# Hocki-Control.net
KiCad netlist of a schematic drawn in EAGLE
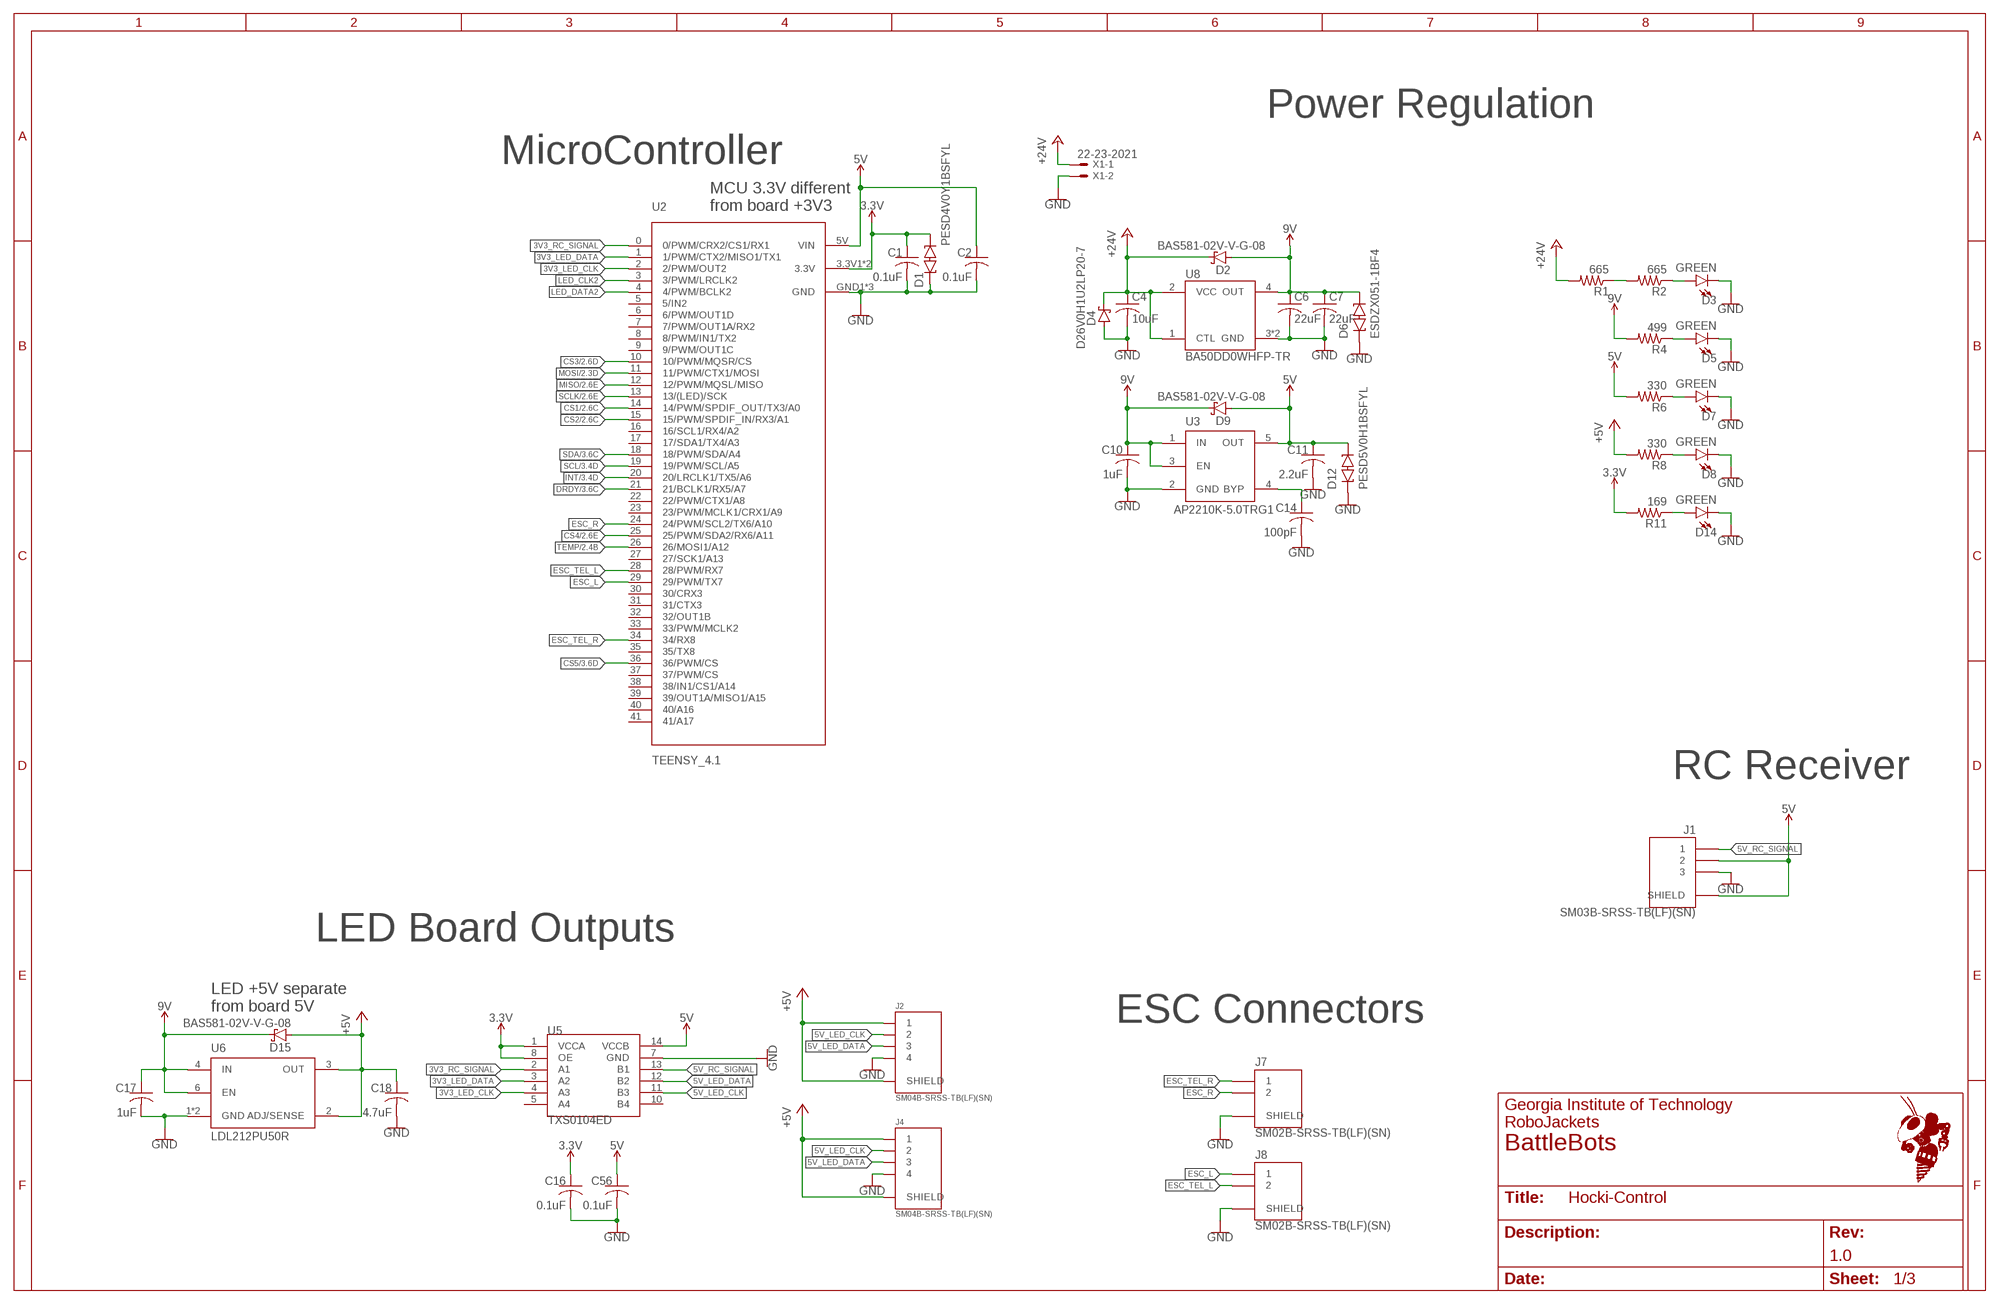
[diagram p0: schematic, sheet 1]
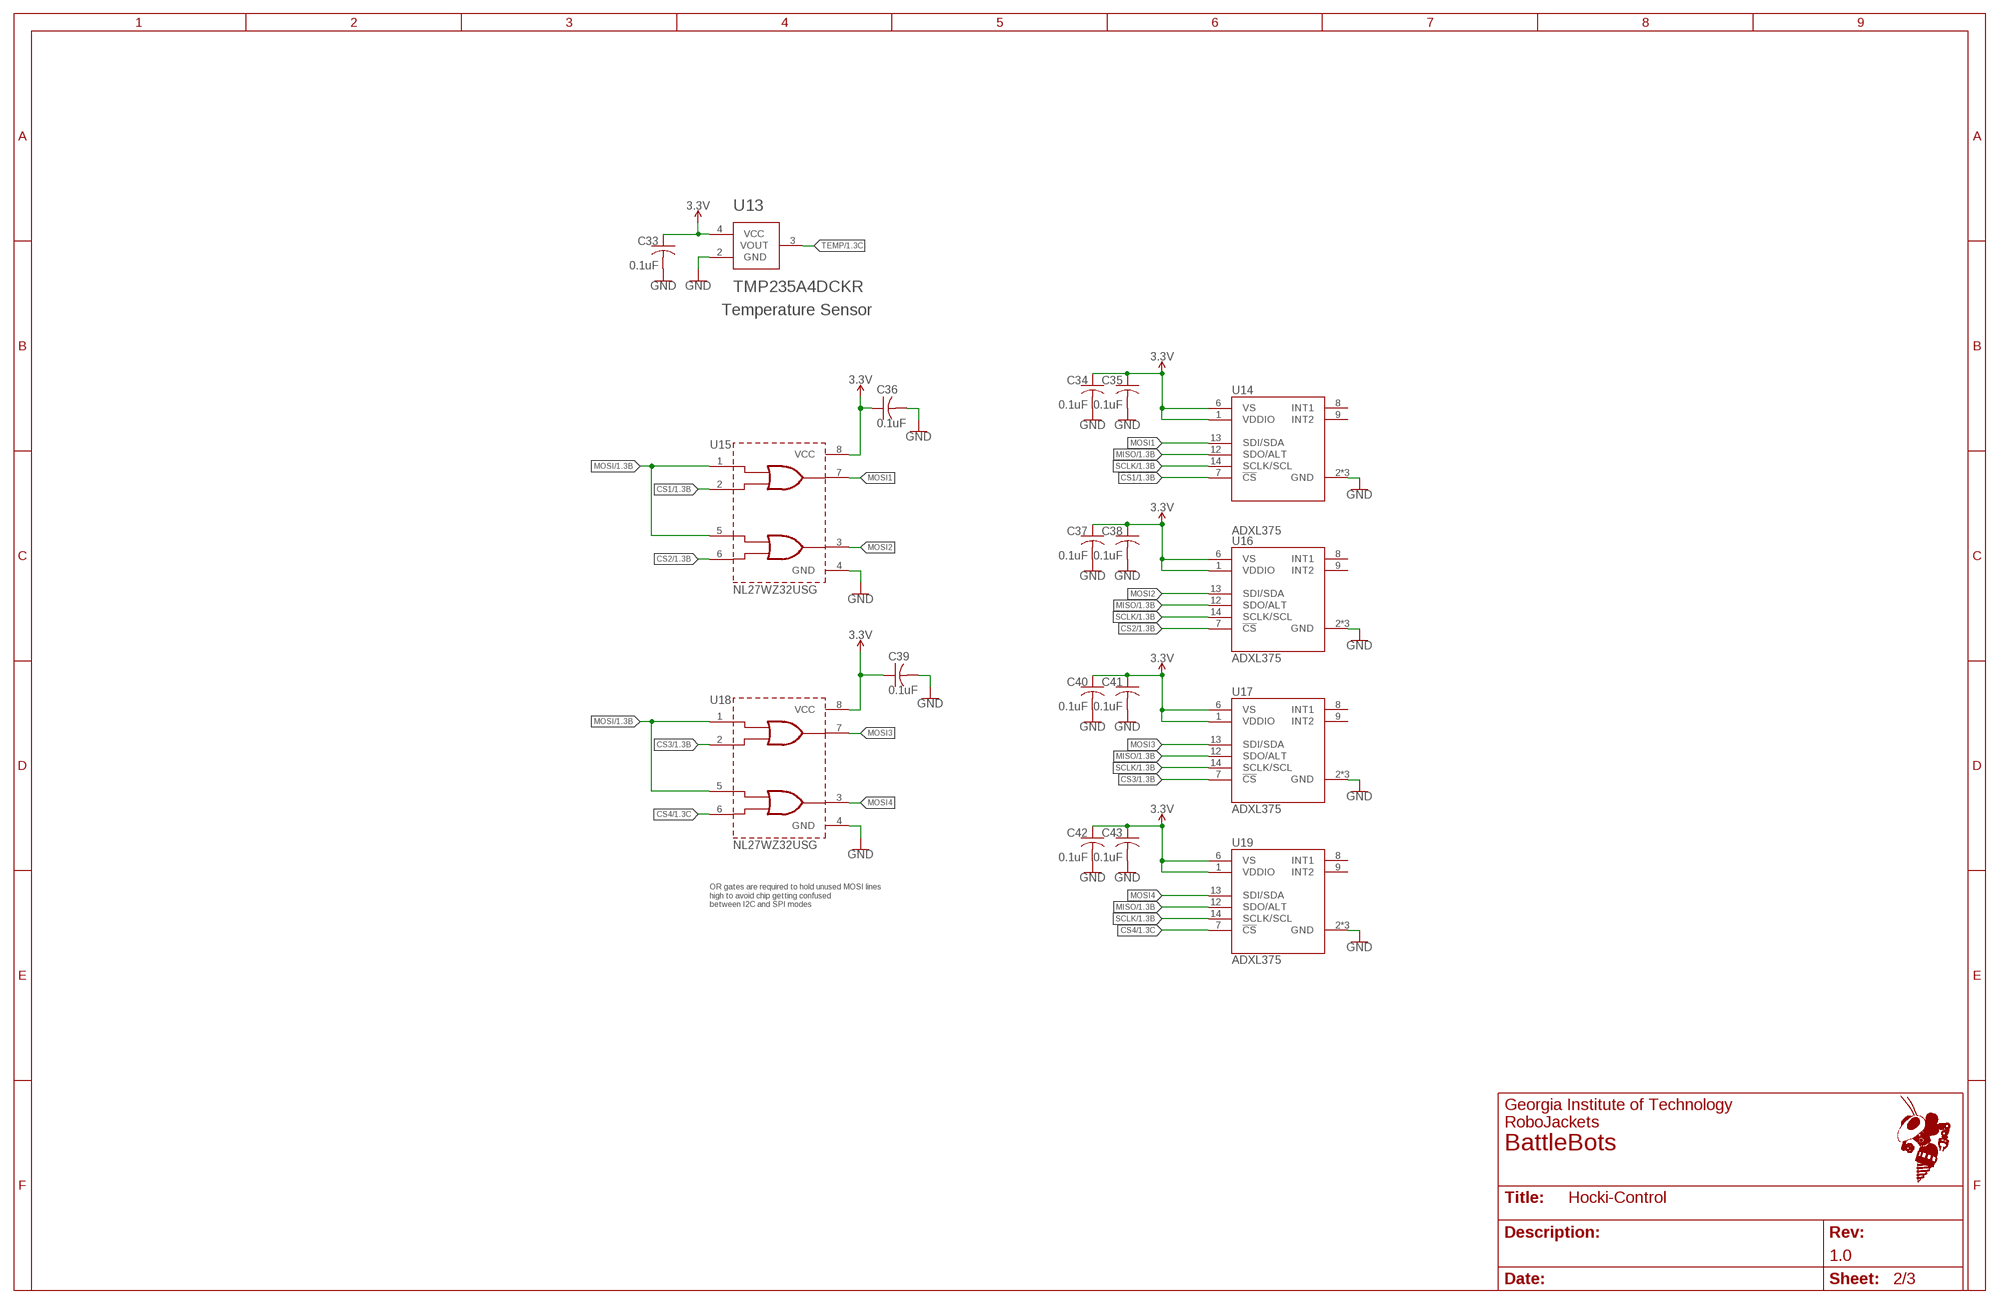
[diagram p1: schematic, sheet 2]
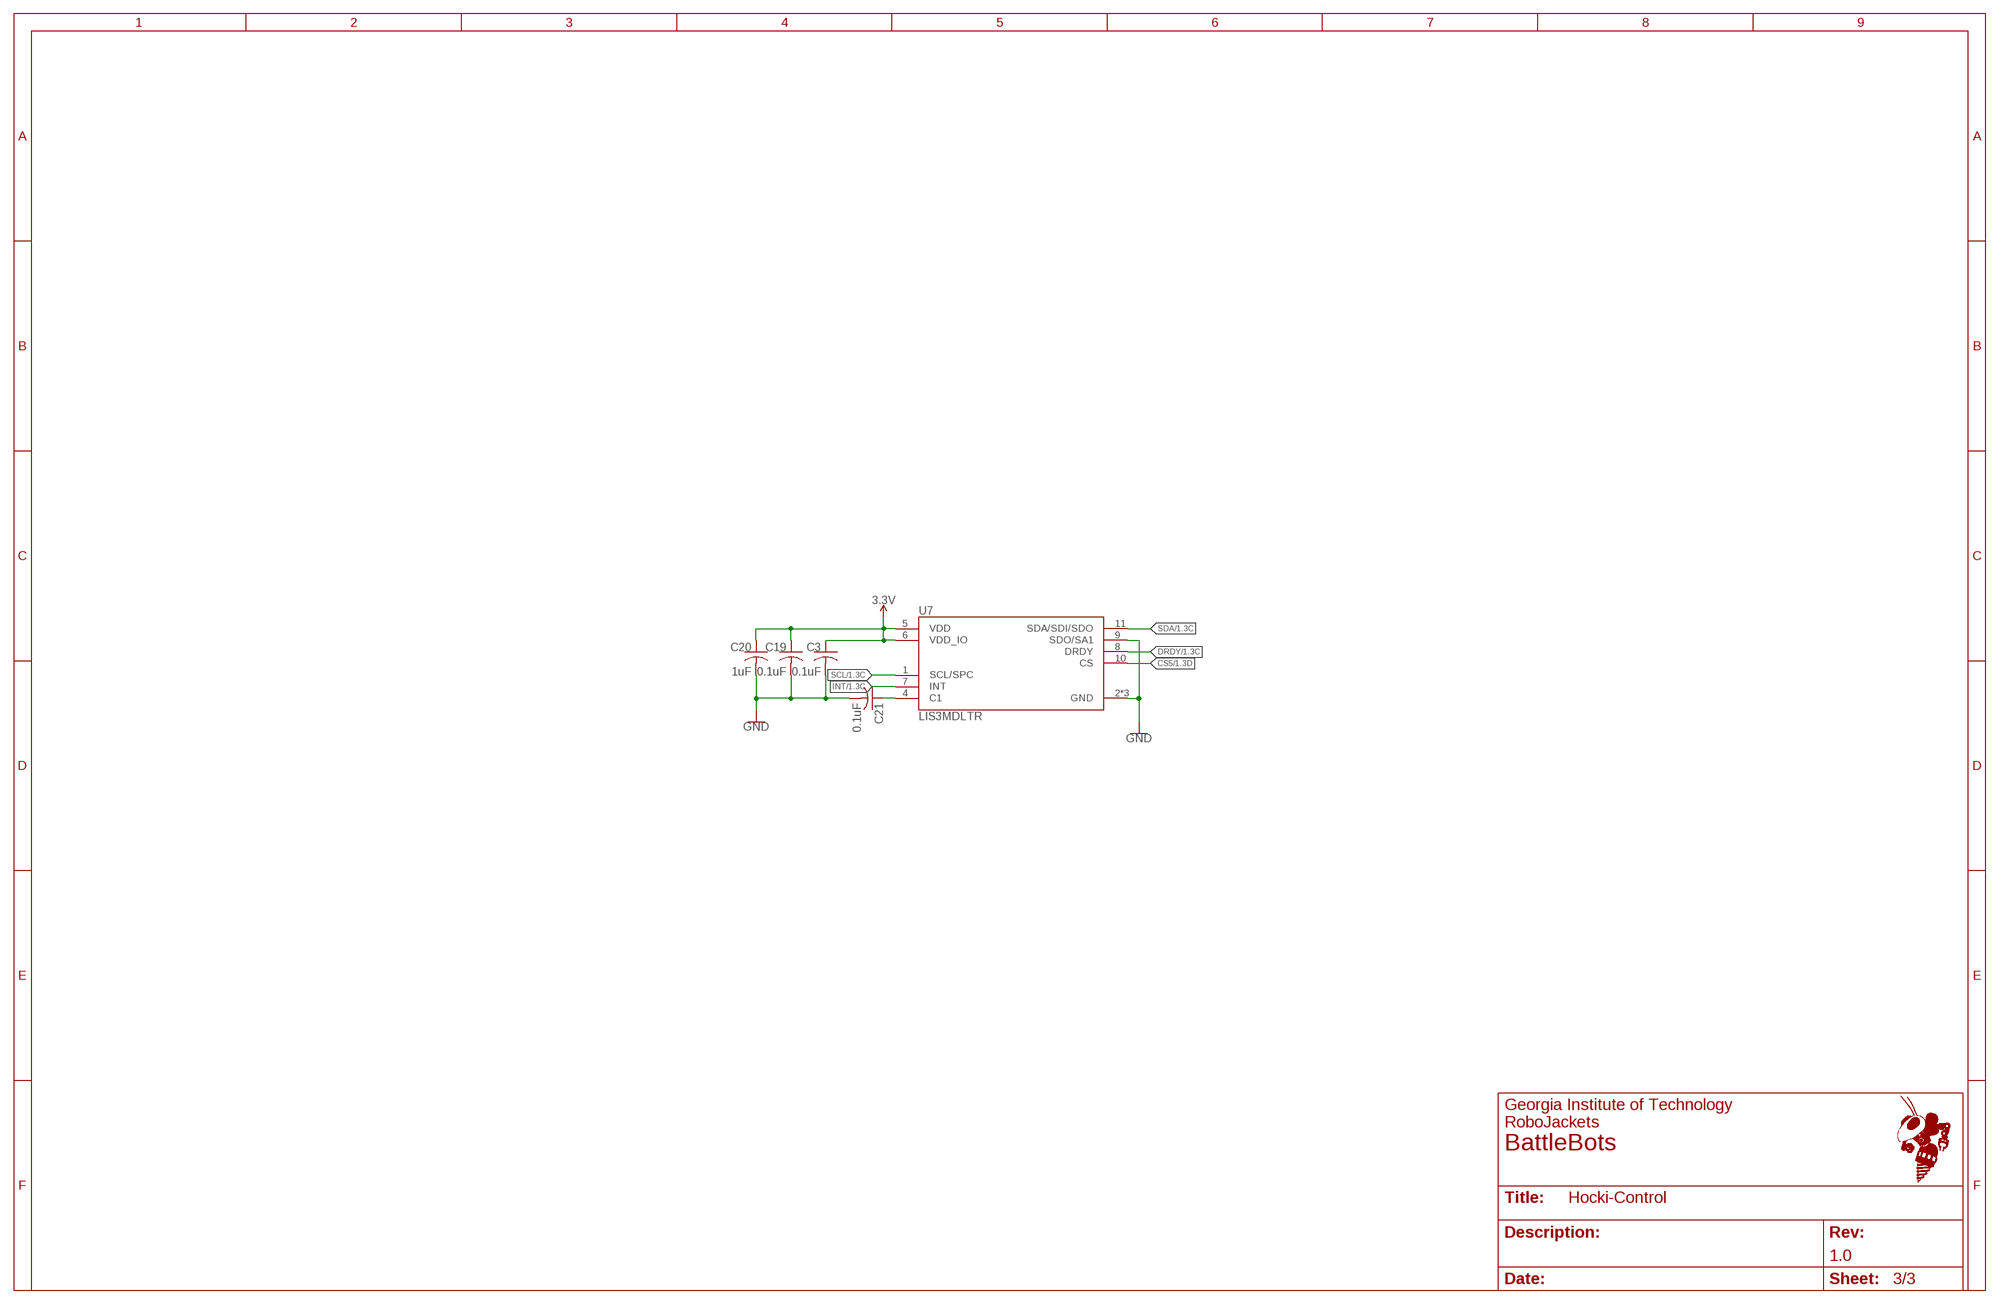
[diagram p2: schematic, sheet 3]

(export (version "E")
  (design (tool "Eeschema 10.0.6"))
  (components
    (comp (ref "C3")
      (value "0.1uF")
      (footprint "eagle-import:C0603")
      (libsource (lib "eagle-import") (part "C-USC0603"))
    )
    (comp (ref "C19")
      (value "0.1uF")
      (footprint "eagle-import:C0603")
      (libsource (lib "eagle-import") (part "C-USC0603"))
    )
    (comp (ref "C20")
      (value "1uF")
      (footprint "eagle-import:C0603")
      (libsource (lib "eagle-import") (part "C-USC0603"))
    )
    (comp (ref "C21")
      (value "0.1uF")
      (footprint "eagle-import:C0603")
      (libsource (lib "eagle-import") (part "C-USC0603"))
    )
    (comp (ref "U7")
      (value "LIS3MDLTR")
      (footprint "eagle-import:LGA-12_2X2X1_STM")
      (libsource (lib "eagle-import") (part "LIS3MDLTR"))
    )
    (comp (ref "C1")
      (value "0.1uF")
      (footprint "eagle-import:C0603")
      (libsource (lib "eagle-import") (part "C-USC0603"))
    )
    (comp (ref "C2")
      (value "0.1uF")
      (footprint "eagle-import:C0603")
      (libsource (lib "eagle-import") (part "C-USC0603"))
    )
    (comp (ref "C4")
      (value "10uF")
      (footprint "eagle-import:C1206")
      (libsource (lib "eagle-import") (part "C-USC1206"))
    )
    (comp (ref "C6")
      (value "22uF")
      (footprint "eagle-import:C1206")
      (libsource (lib "eagle-import") (part "C-USC1206"))
    )
    (comp (ref "C7")
      (value "22uF")
      (footprint "eagle-import:C1206")
      (libsource (lib "eagle-import") (part "C-USC1206"))
    )
    (comp (ref "C10")
      (value "1uF")
      (footprint "eagle-import:C0603")
      (libsource (lib "eagle-import") (part "C-USC0603"))
    )
    (comp (ref "C11")
      (value "2.2uF")
      (footprint "eagle-import:C0603")
      (libsource (lib "eagle-import") (part "C-USC0603"))
    )
    (comp (ref "C14")
      (value "100pF")
      (footprint "eagle-import:C0603")
      (libsource (lib "eagle-import") (part "C-USC0603"))
    )
    (comp (ref "C16")
      (value "0.1uF")
      (footprint "eagle-import:C0603")
      (libsource (lib "eagle-import") (part "C-USC0603"))
    )
    (comp (ref "C17")
      (value "1uF")
      (footprint "eagle-import:C0603")
      (libsource (lib "eagle-import") (part "C-USC0603"))
    )
    (comp (ref "C18")
      (value "4.7uF")
      (footprint "eagle-import:C0603")
      (libsource (lib "eagle-import") (part "C-USC0603"))
    )
    (comp (ref "C56")
      (value "0.1uF")
      (footprint "eagle-import:C0603")
      (libsource (lib "eagle-import") (part "C-USC0603"))
    )
    (comp (ref "D1")
      (value "PESD4V0Y1BSFYL")
      (footprint "eagle-import:DSN0603-2")
      (libsource (lib "eagle-import") (part "PESD4V0Y1BSFYL"))
    )
    (comp (ref "D2")
      (value "BAS581-02V-V-G-08")
      (footprint "eagle-import:SOD-523")
      (libsource (lib "eagle-import") (part "BAS581-02V-V-G-08"))
    )
    (comp (ref "D3")
      (value "GREEN")
      (footprint "eagle-import:LED-0603")
      (libsource (lib "eagle-import") (part "LED-GREEN0603"))
    )
    (comp (ref "D4")
      (value "D26V0H1U2LP20-7")
      (footprint "eagle-import:D26V0H1U2LP20-7")
      (libsource (lib "eagle-import") (part "D26V0H1U2LP20-7"))
    )
    (comp (ref "D5")
      (value "GREEN")
      (footprint "eagle-import:LED-0603")
      (libsource (lib "eagle-import") (part "LED-GREEN0603"))
    )
    (comp (ref "D6")
      (value "ESDZX051-1BF4")
      (footprint "eagle-import:DSN0603-2")
      (libsource (lib "eagle-import") (part "ESDZX051-1BF4"))
    )
    (comp (ref "D7")
      (value "GREEN")
      (footprint "eagle-import:LED-0603")
      (libsource (lib "eagle-import") (part "LED-GREEN0603"))
    )
    (comp (ref "D8")
      (value "GREEN")
      (footprint "eagle-import:LED-0603")
      (libsource (lib "eagle-import") (part "LED-GREEN0603"))
    )
    (comp (ref "D9")
      (value "BAS581-02V-V-G-08")
      (footprint "eagle-import:SOD-523")
      (libsource (lib "eagle-import") (part "BAS581-02V-V-G-08"))
    )
    (comp (ref "D12")
      (value "PESD5V0H1BSFYL")
      (footprint "eagle-import:DSN0603-2")
      (libsource (lib "eagle-import") (part "PESD5V0H1BSFYL"))
    )
    (comp (ref "D14")
      (value "GREEN")
      (footprint "eagle-import:LED-0603")
      (libsource (lib "eagle-import") (part "LED-GREEN0603"))
    )
    (comp (ref "D15")
      (value "BAS581-02V-V-G-08")
      (footprint "eagle-import:SOD-523")
      (libsource (lib "eagle-import") (part "BAS581-02V-V-G-08"))
    )
    (comp (ref "J1")
      (value "SM03B-SRSS-TB(LF)(SN)")
      (footprint "eagle-import:SM03B-SRSS-TB(LF)(SN)")
      (libsource (lib "eagle-import") (part "SM03B-SRSS-TB(LF)(SN)"))
    )
    (comp (ref "J2")
      (value "SM04B-SRSS-TB(LF)(SN)")
      (footprint "eagle-import:SM04B-SRSS-TB(LF)(SN)")
      (libsource (lib "eagle-import") (part "SM04B-SRSS-TB(LF)(SN)"))
    )
    (comp (ref "J4")
      (value "SM04B-SRSS-TB(LF)(SN)")
      (footprint "eagle-import:SM04B-SRSS-TB(LF)(SN)")
      (libsource (lib "eagle-import") (part "SM04B-SRSS-TB(LF)(SN)"))
    )
    (comp (ref "J7")
      (value "SM02B-SRSS-TB(LF)(SN)")
      (footprint "eagle-import:SM02B-SRSS-TB(LF)(SN)")
      (libsource (lib "eagle-import") (part "SM02B-SRSS-TB(LF)(SN)"))
    )
    (comp (ref "J8")
      (value "SM02B-SRSS-TB(LF)(SN)")
      (footprint "eagle-import:SM02B-SRSS-TB(LF)(SN)")
      (libsource (lib "eagle-import") (part "SM02B-SRSS-TB(LF)(SN)"))
    )
    (comp (ref "R1")
      (value "665")
      (footprint "eagle-import:R0603")
      (libsource (lib "eagle-import") (part "R-US_R0603"))
    )
    (comp (ref "R2")
      (value "665")
      (footprint "eagle-import:R0603")
      (libsource (lib "eagle-import") (part "R-US_R0603"))
    )
    (comp (ref "R4")
      (value "499")
      (footprint "eagle-import:R0603")
      (libsource (lib "eagle-import") (part "R-US_R0603"))
    )
    (comp (ref "R6")
      (value "330")
      (footprint "eagle-import:R0603")
      (libsource (lib "eagle-import") (part "R-US_R0603"))
    )
    (comp (ref "R8")
      (value "330")
      (footprint "eagle-import:R0603")
      (libsource (lib "eagle-import") (part "R-US_R0603"))
    )
    (comp (ref "R11")
      (value "169")
      (footprint "eagle-import:R0603")
      (libsource (lib "eagle-import") (part "R-US_R0603"))
    )
    (comp (ref "U2")
      (value "TEENSY_4.1")
      (footprint "eagle-import:TEENSY_4.1")
      (libsource (lib "eagle-import") (part "TEENSY_4.1"))
    )
    (comp (ref "U3")
      (value "AP2210K-5.0TRG1")
      (footprint "eagle-import:SOT-23-5")
      (libsource (lib "eagle-import") (part "AP2210K-TRG15.0"))
    )
    (comp (ref "U5")
      (value "TXS0104ED")
      (footprint "eagle-import:14-SOIC")
      (libsource (lib "eagle-import") (part "TXS0104ED"))
    )
    (comp (ref "U6")
      (value "LDL212PU50R")
      (footprint "eagle-import:DFN6(3X3)")
      (libsource (lib "eagle-import") (part "LDL212PU50R"))
    )
    (comp (ref "U8")
      (value "BA50DD0WHFP-TR")
      (footprint "eagle-import:HRP5")
      (libsource (lib "eagle-import") (part "BA50DD0WHFP-TR"))
    )
    (comp (ref "X1")
      (value "22-23-2021")
      (footprint "eagle-import:22-23-2021")
      (fields (field (name "MF") "MOLEX"))
      (libsource (lib "eagle-import") (part "22-23-2021"))
    )
    (comp (ref "C33")
      (value "0.1uF")
      (footprint "eagle-import:C0603")
      (libsource (lib "eagle-import") (part "C-USC0603"))
    )
    (comp (ref "C34")
      (value "0.1uF")
      (footprint "eagle-import:C0603")
      (libsource (lib "eagle-import") (part "C-USC0603"))
    )
    (comp (ref "C35")
      (value "0.1uF")
      (footprint "eagle-import:C0603")
      (libsource (lib "eagle-import") (part "C-USC0603"))
    )
    (comp (ref "C36")
      (value "0.1uF")
      (footprint "eagle-import:C0603")
      (libsource (lib "eagle-import") (part "C-USC0603"))
    )
    (comp (ref "C37")
      (value "0.1uF")
      (footprint "eagle-import:C0603")
      (libsource (lib "eagle-import") (part "C-USC0603"))
    )
    (comp (ref "C38")
      (value "0.1uF")
      (footprint "eagle-import:C0603")
      (libsource (lib "eagle-import") (part "C-USC0603"))
    )
    (comp (ref "C39")
      (value "0.1uF")
      (footprint "eagle-import:C0603")
      (libsource (lib "eagle-import") (part "C-USC0603"))
    )
    (comp (ref "C40")
      (value "0.1uF")
      (footprint "eagle-import:C0603")
      (libsource (lib "eagle-import") (part "C-USC0603"))
    )
    (comp (ref "C41")
      (value "0.1uF")
      (footprint "eagle-import:C0603")
      (libsource (lib "eagle-import") (part "C-USC0603"))
    )
    (comp (ref "C42")
      (value "0.1uF")
      (footprint "eagle-import:C0603")
      (libsource (lib "eagle-import") (part "C-USC0603"))
    )
    (comp (ref "C43")
      (value "0.1uF")
      (footprint "eagle-import:C0603")
      (libsource (lib "eagle-import") (part "C-USC0603"))
    )
    (comp (ref "U13")
      (value "TMP235A4DCKR")
      (footprint "eagle-import:SOT-353")
      (libsource (lib "eagle-import") (part "TMP235A4DCKR"))
    )
    (comp (ref "U14")
      (value "ADXL375")
      (footprint "eagle-import:14-LGA")
      (libsource (lib "eagle-import") (part "ADXL375"))
    )
    (comp (ref "U15")
      (value "NL27WZ32USG")
      (footprint "eagle-import:US8")
      (libsource (lib "eagle-import") (part "NL27WZ32USG"))
    )
    (comp (ref "U16")
      (value "ADXL375")
      (footprint "eagle-import:14-LGA")
      (libsource (lib "eagle-import") (part "ADXL375"))
    )
    (comp (ref "U17")
      (value "ADXL375")
      (footprint "eagle-import:14-LGA")
      (libsource (lib "eagle-import") (part "ADXL375"))
    )
    (comp (ref "U18")
      (value "NL27WZ32USG")
      (footprint "eagle-import:US8")
      (libsource (lib "eagle-import") (part "NL27WZ32USG"))
    )
    (comp (ref "U19")
      (value "ADXL375")
      (footprint "eagle-import:14-LGA")
      (libsource (lib "eagle-import") (part "ADXL375"))
    )
  )
  (nets
    (net (code "1") (name "+5V") (class "Default")
      (node (ref "C18") (pin "1") (pinfunction "1_1") (pintype "passive"))
      (node (ref "D15") (pin "2") (pinfunction "A_2") (pintype "passive"))
      (node (ref "J2") (pin "1") (pinfunction "1_1") (pintype "passive"))
      (node (ref "J2") (pin "S1") (pinfunction "SHIELD_S1") (pintype "passive"))
      (node (ref "J2") (pin "S2") (pinfunction "SHIELD_S2") (pintype "passive"))
      (node (ref "J4") (pin "1") (pinfunction "1_1") (pintype "passive"))
      (node (ref "J4") (pin "S1") (pinfunction "SHIELD_S1") (pintype "passive"))
      (node (ref "J4") (pin "S2") (pinfunction "SHIELD_S2") (pintype "passive"))
      (node (ref "R8") (pin "2") (pinfunction "2_2") (pintype "passive"))
      (node (ref "U6") (pin "2") (pinfunction "ADJ/SENSE_2") (pintype "bidirectional"))
      (node (ref "U6") (pin "3") (pinfunction "OUT_3") (pintype "passive"))
    )
    (net (code "2") (name "+24V") (class "Default")
      (node (ref "C4") (pin "1") (pinfunction "1_1") (pintype "passive"))
      (node (ref "D2") (pin "1") (pinfunction "C_1") (pintype "passive"))
      (node (ref "D4") (pin "1") (pinfunction "C_1") (pintype "passive"))
      (node (ref "R1") (pin "2") (pinfunction "2_2") (pintype "passive"))
      (node (ref "U8") (pin "1") (pinfunction "CTL_1") (pintype "input"))
      (node (ref "U8") (pin "2") (pinfunction "VCC_2") (pintype "power_in"))
      (node (ref "X1") (pin "1") (pinfunction "S_1") (pintype "passive"))
    )
    (net (code "3") (name "3.3V") (class "Default")
      (node (ref "C1") (pin "1") (pinfunction "1_1") (pintype "passive"))
      (node (ref "C16") (pin "1") (pinfunction "1_1") (pintype "passive"))
      (node (ref "C19") (pin "1") (pinfunction "1_1") (pintype "passive"))
      (node (ref "C20") (pin "1") (pinfunction "1_1") (pintype "passive"))
      (node (ref "C3") (pin "1") (pinfunction "1_1") (pintype "passive"))
      (node (ref "C33") (pin "1") (pinfunction "1_1") (pintype "passive"))
      (node (ref "C34") (pin "1") (pinfunction "1_1") (pintype "passive"))
      (node (ref "C35") (pin "1") (pinfunction "1_1") (pintype "passive"))
      (node (ref "C36") (pin "1") (pinfunction "1_1") (pintype "passive"))
      (node (ref "C37") (pin "1") (pinfunction "1_1") (pintype "passive"))
      (node (ref "C38") (pin "1") (pinfunction "1_1") (pintype "passive"))
      (node (ref "C39") (pin "1") (pinfunction "1_1") (pintype "passive"))
      (node (ref "C40") (pin "1") (pinfunction "1_1") (pintype "passive"))
      (node (ref "C41") (pin "1") (pinfunction "1_1") (pintype "passive"))
      (node (ref "C42") (pin "1") (pinfunction "1_1") (pintype "passive"))
      (node (ref "C43") (pin "1") (pinfunction "1_1") (pintype "passive"))
      (node (ref "D1") (pin "C2") (pinfunction "C2_C2") (pintype "passive"))
      (node (ref "R11") (pin "2") (pinfunction "2_2") (pintype "passive"))
      (node (ref "U13") (pin "4") (pinfunction "VCC_4") (pintype "passive"))
      (node (ref "U14") (pin "1") (pinfunction "VDDIO_1") (pintype "passive"))
      (node (ref "U14") (pin "6") (pinfunction "VS_6") (pintype "passive"))
      (node (ref "U15") (pin "8") (pinfunction "VCC_8") (pintype "passive"))
      (node (ref "U16") (pin "1") (pinfunction "VDDIO_1") (pintype "passive"))
      (node (ref "U16") (pin "6") (pinfunction "VS_6") (pintype "passive"))
      (node (ref "U17") (pin "1") (pinfunction "VDDIO_1") (pintype "passive"))
      (node (ref "U17") (pin "6") (pinfunction "VS_6") (pintype "passive"))
      (node (ref "U18") (pin "8") (pinfunction "VCC_8") (pintype "passive"))
      (node (ref "U19") (pin "1") (pinfunction "VDDIO_1") (pintype "passive"))
      (node (ref "U19") (pin "6") (pinfunction "VS_6") (pintype "passive"))
      (node (ref "U2") (pin "3.3V1") (pinfunction "3.3V_3.3V1") (pintype "passive"))
      (node (ref "U2") (pin "3.3V2") (pinfunction "3.3V_3.3V2") (pintype "passive"))
      (node (ref "U5") (pin "1") (pinfunction "VCCA_1") (pintype "passive"))
      (node (ref "U5") (pin "8") (pinfunction "OE_8") (pintype "passive"))
      (node (ref "U7") (pin "5") (pinfunction "VDD_5") (pintype "passive"))
      (node (ref "U7") (pin "6") (pinfunction "VDD_IO_6") (pintype "passive"))
    )
    (net (code "4") (name "3V3_LED_CLK") (class "Default")
      (node (ref "U2") (pin "2") (pinfunction "2/PWM/OUT2_2") (pintype "passive"))
      (node (ref "U5") (pin "4") (pinfunction "A3_4") (pintype "passive"))
    )
    (net (code "5") (name "3V3_LED_DATA") (class "Default")
      (node (ref "U2") (pin "1") (pinfunction "1/PWM/CTX2/MISO1/TX1_1") (pintype "passive"))
      (node (ref "U5") (pin "3") (pinfunction "A2_3") (pintype "passive"))
    )
    (net (code "6") (name "3V3_RC_SIGNAL") (class "Default")
      (node (ref "U2") (pin "0") (pinfunction "0/PWM/CRX2/CS1/RX1_0") (pintype "passive"))
      (node (ref "U5") (pin "2") (pinfunction "A1_2") (pintype "passive"))
    )
    (net (code "7") (name "5V") (class "Default")
      (node (ref "C11") (pin "1") (pinfunction "1_1") (pintype "passive"))
      (node (ref "C2") (pin "1") (pinfunction "1_1") (pintype "passive"))
      (node (ref "C56") (pin "1") (pinfunction "1_1") (pintype "passive"))
      (node (ref "D12") (pin "C2") (pinfunction "C2_C2") (pintype "passive"))
      (node (ref "D9") (pin "2") (pinfunction "A_2") (pintype "passive"))
      (node (ref "J1") (pin "2") (pinfunction "2_2") (pintype "passive"))
      (node (ref "J1") (pin "S1") (pinfunction "SHIELD_S1") (pintype "passive"))
      (node (ref "J1") (pin "S2") (pinfunction "SHIELD_S2") (pintype "passive"))
      (node (ref "R6") (pin "2") (pinfunction "2_2") (pintype "passive"))
      (node (ref "U2") (pin "5V") (pinfunction "VIN_5V") (pintype "passive"))
      (node (ref "U3") (pin "5") (pinfunction "OUT_5") (pintype "passive"))
      (node (ref "U5") (pin "14") (pinfunction "VCCB_14") (pintype "passive"))
    )
    (net (code "8") (name "5V_LED_CLK") (class "Default")
      (node (ref "J2") (pin "2") (pinfunction "2_2") (pintype "passive"))
      (node (ref "J4") (pin "2") (pinfunction "2_2") (pintype "passive"))
      (node (ref "U5") (pin "11") (pinfunction "B3_11") (pintype "passive"))
    )
    (net (code "9") (name "5V_LED_DATA") (class "Default")
      (node (ref "J2") (pin "3") (pinfunction "3_3") (pintype "passive"))
      (node (ref "J4") (pin "3") (pinfunction "3_3") (pintype "passive"))
      (node (ref "U5") (pin "12") (pinfunction "B2_12") (pintype "passive"))
    )
    (net (code "10") (name "5V_RC_SIGNAL") (class "Default")
      (node (ref "J1") (pin "1") (pinfunction "1_1") (pintype "passive"))
      (node (ref "U5") (pin "13") (pinfunction "B1_13") (pintype "passive"))
    )
    (net (code "11") (name "9V") (class "Default")
      (node (ref "C10") (pin "1") (pinfunction "1_1") (pintype "passive"))
      (node (ref "C17") (pin "1") (pinfunction "1_1") (pintype "passive"))
      (node (ref "C6") (pin "1") (pinfunction "1_1") (pintype "passive"))
      (node (ref "C7") (pin "1") (pinfunction "1_1") (pintype "passive"))
      (node (ref "D15") (pin "1") (pinfunction "C_1") (pintype "passive"))
      (node (ref "D2") (pin "2") (pinfunction "A_2") (pintype "passive"))
      (node (ref "D6") (pin "C2") (pinfunction "C2_C2") (pintype "passive"))
      (node (ref "D9") (pin "1") (pinfunction "C_1") (pintype "passive"))
      (node (ref "R4") (pin "2") (pinfunction "2_2") (pintype "passive"))
      (node (ref "U3") (pin "1") (pinfunction "IN_1") (pintype "passive"))
      (node (ref "U3") (pin "3") (pinfunction "EN_3") (pintype "passive"))
      (node (ref "U6") (pin "4") (pinfunction "IN_4") (pintype "passive"))
      (node (ref "U6") (pin "6") (pinfunction "EN_6") (pintype "passive"))
      (node (ref "U8") (pin "4") (pinfunction "OUT_4") (pintype "output"))
    )
    (net (code "12") (name "CS1") (class "Default")
      (node (ref "U14") (pin "7") (pinfunction "~{CS}_7") (pintype "passive"))
      (node (ref "U15") (pin "2") (pinfunction "B1_2") (pintype "passive"))
      (node (ref "U2") (pin "14") (pinfunction "14/PWM/SPDIF_OUT/TX3/A0_14") (pintype "passive"))
    )
    (net (code "13") (name "CS2") (class "Default")
      (node (ref "U15") (pin "6") (pinfunction "B2_6") (pintype "passive"))
      (node (ref "U16") (pin "7") (pinfunction "~{CS}_7") (pintype "passive"))
      (node (ref "U2") (pin "15") (pinfunction "15/PWM/SPDIF_IN/RX3/A1_15") (pintype "passive"))
    )
    (net (code "14") (name "CS3") (class "Default")
      (node (ref "U17") (pin "7") (pinfunction "~{CS}_7") (pintype "passive"))
      (node (ref "U18") (pin "2") (pinfunction "B1_2") (pintype "passive"))
      (node (ref "U2") (pin "10") (pinfunction "10/PWM/MQSR/CS_10") (pintype "passive"))
    )
    (net (code "15") (name "CS4") (class "Default")
      (node (ref "U18") (pin "6") (pinfunction "B2_6") (pintype "passive"))
      (node (ref "U19") (pin "7") (pinfunction "~{CS}_7") (pintype "passive"))
      (node (ref "U2") (pin "25") (pinfunction "25/PWM/SDA2/RX6/A11_25") (pintype "passive"))
    )
    (net (code "16") (name "CS5") (class "Default")
      (node (ref "U2") (pin "36") (pinfunction "36/PWM/CS_36") (pintype "passive"))
      (node (ref "U7") (pin "10") (pinfunction "CS_10") (pintype "passive"))
    )
    (net (code "17") (name "DRDY") (class "Default")
      (node (ref "U2") (pin "21") (pinfunction "21/BCLK1/RX5/A7_21") (pintype "passive"))
      (node (ref "U7") (pin "8") (pinfunction "DRDY_8") (pintype "passive"))
    )
    (net (code "18") (name "ESC_L") (class "Default")
      (node (ref "J8") (pin "1") (pinfunction "1_1") (pintype "passive"))
      (node (ref "U2") (pin "29") (pinfunction "29/PWM/TX7_29") (pintype "passive"))
    )
    (net (code "19") (name "ESC_R") (class "Default")
      (node (ref "J7") (pin "2") (pinfunction "2_2") (pintype "passive"))
      (node (ref "U2") (pin "24") (pinfunction "24/PWM/SCL2/TX6/A10_24") (pintype "passive"))
    )
    (net (code "20") (name "ESC_TEL_L") (class "Default")
      (node (ref "J8") (pin "2") (pinfunction "2_2") (pintype "passive"))
      (node (ref "U2") (pin "28") (pinfunction "28/PWM/RX7_28") (pintype "passive"))
    )
    (net (code "21") (name "ESC_TEL_R") (class "Default")
      (node (ref "J7") (pin "1") (pinfunction "1_1") (pintype "passive"))
      (node (ref "U2") (pin "34") (pinfunction "34/RX8_34") (pintype "passive"))
    )
    (net (code "22") (name "GND") (class "Default")
      (node (ref "C1") (pin "2") (pinfunction "2_2") (pintype "passive"))
      (node (ref "C10") (pin "2") (pinfunction "2_2") (pintype "passive"))
      (node (ref "C11") (pin "2") (pinfunction "2_2") (pintype "passive"))
      (node (ref "C14") (pin "2") (pinfunction "2_2") (pintype "passive"))
      (node (ref "C16") (pin "2") (pinfunction "2_2") (pintype "passive"))
      (node (ref "C17") (pin "2") (pinfunction "2_2") (pintype "passive"))
      (node (ref "C18") (pin "2") (pinfunction "2_2") (pintype "passive"))
      (node (ref "C19") (pin "2") (pinfunction "2_2") (pintype "passive"))
      (node (ref "C2") (pin "2") (pinfunction "2_2") (pintype "passive"))
      (node (ref "C20") (pin "2") (pinfunction "2_2") (pintype "passive"))
      (node (ref "C21") (pin "2") (pinfunction "2_2") (pintype "passive"))
      (node (ref "C3") (pin "2") (pinfunction "2_2") (pintype "passive"))
      (node (ref "C33") (pin "2") (pinfunction "2_2") (pintype "passive"))
      (node (ref "C34") (pin "2") (pinfunction "2_2") (pintype "passive"))
      (node (ref "C35") (pin "2") (pinfunction "2_2") (pintype "passive"))
      (node (ref "C36") (pin "2") (pinfunction "2_2") (pintype "passive"))
      (node (ref "C37") (pin "2") (pinfunction "2_2") (pintype "passive"))
      (node (ref "C38") (pin "2") (pinfunction "2_2") (pintype "passive"))
      (node (ref "C39") (pin "2") (pinfunction "2_2") (pintype "passive"))
      (node (ref "C4") (pin "2") (pinfunction "2_2") (pintype "passive"))
      (node (ref "C40") (pin "2") (pinfunction "2_2") (pintype "passive"))
      (node (ref "C41") (pin "2") (pinfunction "2_2") (pintype "passive"))
      (node (ref "C42") (pin "2") (pinfunction "2_2") (pintype "passive"))
      (node (ref "C43") (pin "2") (pinfunction "2_2") (pintype "passive"))
      (node (ref "C56") (pin "2") (pinfunction "2_2") (pintype "passive"))
      (node (ref "C6") (pin "2") (pinfunction "2_2") (pintype "passive"))
      (node (ref "C7") (pin "2") (pinfunction "2_2") (pintype "passive"))
      (node (ref "D1") (pin "C1") (pinfunction "C1_C1") (pintype "passive"))
      (node (ref "D12") (pin "C1") (pinfunction "C1_C1") (pintype "passive"))
      (node (ref "D14") (pin "C") (pinfunction "C_C") (pintype "passive"))
      (node (ref "D3") (pin "C") (pinfunction "C_C") (pintype "passive"))
      (node (ref "D4") (pin "2") (pinfunction "A_2") (pintype "passive"))
      (node (ref "D5") (pin "C") (pinfunction "C_C") (pintype "passive"))
      (node (ref "D6") (pin "C1") (pinfunction "C1_C1") (pintype "passive"))
      (node (ref "D7") (pin "C") (pinfunction "C_C") (pintype "passive"))
      (node (ref "D8") (pin "C") (pinfunction "C_C") (pintype "passive"))
      (node (ref "J1") (pin "3") (pinfunction "3_3") (pintype "passive"))
      (node (ref "J2") (pin "4") (pinfunction "4_4") (pintype "passive"))
      (node (ref "J4") (pin "4") (pinfunction "4_4") (pintype "passive"))
      (node (ref "J7") (pin "S1") (pinfunction "SHIELD_S1") (pintype "passive"))
      (node (ref "J7") (pin "S2") (pinfunction "SHIELD_S2") (pintype "passive"))
      (node (ref "J8") (pin "S1") (pinfunction "SHIELD_S1") (pintype "passive"))
      (node (ref "J8") (pin "S2") (pinfunction "SHIELD_S2") (pintype "passive"))
      (node (ref "U13") (pin "2") (pinfunction "GND_2") (pintype "passive"))
      (node (ref "U14") (pin "2") (pinfunction "GND_2") (pintype "passive"))
      (node (ref "U14") (pin "4") (pinfunction "GND_4") (pintype "passive"))
      (node (ref "U14") (pin "5") (pinfunction "GND_5") (pintype "passive"))
      (node (ref "U15") (pin "4") (pinfunction "GND_4") (pintype "passive"))
      (node (ref "U16") (pin "2") (pinfunction "GND_2") (pintype "passive"))
      (node (ref "U16") (pin "4") (pinfunction "GND_4") (pintype "passive"))
      (node (ref "U16") (pin "5") (pinfunction "GND_5") (pintype "passive"))
      (node (ref "U17") (pin "2") (pinfunction "GND_2") (pintype "passive"))
      (node (ref "U17") (pin "4") (pinfunction "GND_4") (pintype "passive"))
      (node (ref "U17") (pin "5") (pinfunction "GND_5") (pintype "passive"))
      (node (ref "U18") (pin "4") (pinfunction "GND_4") (pintype "passive"))
      (node (ref "U19") (pin "2") (pinfunction "GND_2") (pintype "passive"))
      (node (ref "U19") (pin "4") (pinfunction "GND_4") (pintype "passive"))
      (node (ref "U19") (pin "5") (pinfunction "GND_5") (pintype "passive"))
      (node (ref "U2") (pin "GND1") (pinfunction "GND_GND1") (pintype "passive"))
      (node (ref "U2") (pin "GND2") (pinfunction "GND_GND2") (pintype "passive"))
      (node (ref "U2") (pin "GND3") (pinfunction "GND_GND3") (pintype "passive"))
      (node (ref "U3") (pin "2") (pinfunction "GND_2") (pintype "passive"))
      (node (ref "U5") (pin "7") (pinfunction "GND_7") (pintype "passive"))
      (node (ref "U6") (pin "1") (pinfunction "GND_1") (pintype "passive"))
      (node (ref "U6") (pin "7") (pinfunction "GND_7") (pintype "passive"))
      (node (ref "U7") (pin "12") (pinfunction "GND_12") (pintype "passive"))
      (node (ref "U7") (pin "2") (pinfunction "GND_2") (pintype "passive"))
      (node (ref "U7") (pin "3") (pinfunction "GND_3") (pintype "passive"))
      (node (ref "U7") (pin "9") (pinfunction "SDO/SA1_9") (pintype "passive"))
      (node (ref "U8") (pin "3") (pinfunction "GND_3") (pintype "power_in"))
      (node (ref "U8") (pin "6") (pinfunction "GND_6") (pintype "power_in"))
      (node (ref "X1") (pin "2") (pinfunction "S_2") (pintype "passive"))
    )
    (net (code "23") (name "INT") (class "Default")
      (node (ref "U2") (pin "20") (pinfunction "20/LRCLK1/TX5/A6_20") (pintype "passive"))
      (node (ref "U7") (pin "7") (pinfunction "INT_7") (pintype "passive"))
    )
    (net (code "24") (name "LED_CLK2") (class "Default")
      (node (ref "U2") (pin "3") (pinfunction "3/PWM/LRCLK2_3") (pintype "passive"))
    )
    (net (code "25") (name "LED_DATA2") (class "Default")
      (node (ref "U2") (pin "4") (pinfunction "4/PWM/BCLK2_4") (pintype "passive"))
    )
    (net (code "26") (name "MISO") (class "Default")
      (node (ref "U14") (pin "12") (pinfunction "SDO/ALT_12") (pintype "passive"))
      (node (ref "U16") (pin "12") (pinfunction "SDO/ALT_12") (pintype "passive"))
      (node (ref "U17") (pin "12") (pinfunction "SDO/ALT_12") (pintype "passive"))
      (node (ref "U19") (pin "12") (pinfunction "SDO/ALT_12") (pintype "passive"))
      (node (ref "U2") (pin "12") (pinfunction "12/PWM/MQSL/MISO_12") (pintype "passive"))
    )
    (net (code "27") (name "MOSI") (class "Default")
      (node (ref "U15") (pin "1") (pinfunction "A1_1") (pintype "passive"))
      (node (ref "U15") (pin "5") (pinfunction "A2_5") (pintype "passive"))
      (node (ref "U18") (pin "1") (pinfunction "A1_1") (pintype "passive"))
      (node (ref "U18") (pin "5") (pinfunction "A2_5") (pintype "passive"))
      (node (ref "U2") (pin "11") (pinfunction "11/PWM/CTX1/MOSI_11") (pintype "passive"))
    )
    (net (code "28") (name "MOSI1") (class "Default")
      (node (ref "U14") (pin "13") (pinfunction "SDI/SDA_13") (pintype "passive"))
      (node (ref "U15") (pin "7") (pinfunction "Y1_7") (pintype "passive"))
    )
    (net (code "29") (name "MOSI2") (class "Default")
      (node (ref "U15") (pin "3") (pinfunction "Y2_3") (pintype "passive"))
      (node (ref "U16") (pin "13") (pinfunction "SDI/SDA_13") (pintype "passive"))
    )
    (net (code "30") (name "MOSI3") (class "Default")
      (node (ref "U17") (pin "13") (pinfunction "SDI/SDA_13") (pintype "passive"))
      (node (ref "U18") (pin "7") (pinfunction "Y1_7") (pintype "passive"))
    )
    (net (code "31") (name "MOSI4") (class "Default")
      (node (ref "U18") (pin "3") (pinfunction "Y2_3") (pintype "passive"))
      (node (ref "U19") (pin "13") (pinfunction "SDI/SDA_13") (pintype "passive"))
    )
    (net (code "32") (name "Net-(D3-PadA)") (class "Default")
      (node (ref "D3") (pin "A") (pinfunction "A_A") (pintype "passive"))
      (node (ref "R2") (pin "1") (pinfunction "1_1") (pintype "passive"))
    )
    (net (code "33") (name "Net-(D5-PadA)") (class "Default")
      (node (ref "D5") (pin "A") (pinfunction "A_A") (pintype "passive"))
      (node (ref "R4") (pin "1") (pinfunction "1_1") (pintype "passive"))
    )
    (net (code "34") (name "Net-(D7-PadA)") (class "Default")
      (node (ref "D7") (pin "A") (pinfunction "A_A") (pintype "passive"))
      (node (ref "R6") (pin "1") (pinfunction "1_1") (pintype "passive"))
    )
    (net (code "35") (name "Net-(D8-PadA)") (class "Default")
      (node (ref "D8") (pin "A") (pinfunction "A_A") (pintype "passive"))
      (node (ref "R8") (pin "1") (pinfunction "1_1") (pintype "passive"))
    )
    (net (code "36") (name "Net-(D14-PadA)") (class "Default")
      (node (ref "D14") (pin "A") (pinfunction "A_A") (pintype "passive"))
      (node (ref "R11") (pin "1") (pinfunction "1_1") (pintype "passive"))
    )
    (net (code "37") (name "Net-(R1-Pad1)") (class "Default")
      (node (ref "R1") (pin "1") (pinfunction "1_1") (pintype "passive"))
      (node (ref "R2") (pin "2") (pinfunction "2_2") (pintype "passive"))
    )
    (net (code "38") (name "Net-(U3-BYP)") (class "Default")
      (node (ref "C14") (pin "1") (pinfunction "1_1") (pintype "passive"))
      (node (ref "U3") (pin "4") (pinfunction "BYP_4") (pintype "bidirectional"))
    )
    (net (code "39") (name "Net-(U7-C1)") (class "Default")
      (node (ref "C21") (pin "1") (pinfunction "1_1") (pintype "passive"))
      (node (ref "U7") (pin "4") (pinfunction "C1_4") (pintype "passive"))
    )
    (net (code "40") (name "SCL") (class "Default")
      (node (ref "U2") (pin "19") (pinfunction "19/PWM/SCL/A5_19") (pintype "passive"))
      (node (ref "U7") (pin "1") (pinfunction "SCL/SPC_1") (pintype "passive"))
    )
    (net (code "41") (name "SCLK") (class "Default")
      (node (ref "U14") (pin "14") (pinfunction "SCLK/SCL_14") (pintype "passive"))
      (node (ref "U16") (pin "14") (pinfunction "SCLK/SCL_14") (pintype "passive"))
      (node (ref "U17") (pin "14") (pinfunction "SCLK/SCL_14") (pintype "passive"))
      (node (ref "U19") (pin "14") (pinfunction "SCLK/SCL_14") (pintype "passive"))
      (node (ref "U2") (pin "13") (pinfunction "13/(LED)/SCK_13") (pintype "passive"))
    )
    (net (code "42") (name "SDA") (class "Default")
      (node (ref "U2") (pin "18") (pinfunction "18/PWM/SDA/A4_18") (pintype "passive"))
      (node (ref "U7") (pin "11") (pinfunction "SDA/SDI/SDO_11") (pintype "passive"))
    )
    (net (code "43") (name "TEMP") (class "Default")
      (node (ref "U13") (pin "3") (pinfunction "VOUT_3") (pintype "passive"))
      (node (ref "U2") (pin "26") (pinfunction "26/MOSI1/A12_26") (pintype "passive"))
    )
    (net (code "44") (name "unconnected-(U2-5{slash}IN2-Pad5)") (class "Default")
      (node (ref "U2") (pin "5") (pinfunction "5/IN2_5") (pintype "passive"))
    )
    (net (code "45") (name "unconnected-(U2-6{slash}PWM{slash}OUT1D-Pad6)") (class "Default")
      (node (ref "U2") (pin "6") (pinfunction "6/PWM/OUT1D_6") (pintype "passive"))
    )
    (net (code "46") (name "unconnected-(U2-7{slash}PWM{slash}OUT1A{slash}RX2-Pad7)") (class "Default")
      (node (ref "U2") (pin "7") (pinfunction "7/PWM/OUT1A/RX2_7") (pintype "passive"))
    )
    (net (code "47") (name "unconnected-(U2-8{slash}PWM{slash}IN1{slash}TX2-Pad8)") (class "Default")
      (node (ref "U2") (pin "8") (pinfunction "8/PWM/IN1/TX2_8") (pintype "passive"))
    )
    (net (code "48") (name "unconnected-(U2-9{slash}PWM{slash}OUT1C-Pad9)") (class "Default")
      (node (ref "U2") (pin "9") (pinfunction "9/PWM/OUT1C_9") (pintype "passive"))
    )
    (net (code "49") (name "unconnected-(U2-16{slash}SCL1{slash}RX4{slash}A2-Pad16)") (class "Default")
      (node (ref "U2") (pin "16") (pinfunction "16/SCL1/RX4/A2_16") (pintype "passive"))
    )
    (net (code "50") (name "unconnected-(U2-17{slash}SDA1{slash}TX4{slash}A3-Pad17)") (class "Default")
      (node (ref "U2") (pin "17") (pinfunction "17/SDA1/TX4/A3_17") (pintype "passive"))
    )
    (net (code "51") (name "unconnected-(U2-22{slash}PWM{slash}CTX1{slash}A8-Pad22)") (class "Default")
      (node (ref "U2") (pin "22") (pinfunction "22/PWM/CTX1/A8_22") (pintype "passive"))
    )
    (net (code "52") (name "unconnected-(U2-23{slash}PWM{slash}MCLK1{slash}CRX1{slash}A9-Pad23)") (class "Default")
      (node (ref "U2") (pin "23") (pinfunction "23/PWM/MCLK1/CRX1/A9_23") (pintype "passive"))
    )
    (net (code "53") (name "unconnected-(U2-27{slash}SCK1{slash}A13-Pad27)") (class "Default")
      (node (ref "U2") (pin "27") (pinfunction "27/SCK1/A13_27") (pintype "passive"))
    )
    (net (code "54") (name "unconnected-(U2-30{slash}CRX3-Pad30)") (class "Default")
      (node (ref "U2") (pin "30") (pinfunction "30/CRX3_30") (pintype "passive"))
    )
    (net (code "55") (name "unconnected-(U2-31{slash}CTX3-Pad31)") (class "Default")
      (node (ref "U2") (pin "31") (pinfunction "31/CTX3_31") (pintype "passive"))
    )
    (net (code "56") (name "unconnected-(U2-32{slash}OUT1B-Pad32)") (class "Default")
      (node (ref "U2") (pin "32") (pinfunction "32/OUT1B_32") (pintype "passive"))
    )
    (net (code "57") (name "unconnected-(U2-33{slash}PWM{slash}MCLK2-Pad33)") (class "Default")
      (node (ref "U2") (pin "33") (pinfunction "33/PWM/MCLK2_33") (pintype "passive"))
    )
    (net (code "58") (name "unconnected-(U2-35{slash}TX8-Pad35)") (class "Default")
      (node (ref "U2") (pin "35") (pinfunction "35/TX8_35") (pintype "passive"))
    )
    (net (code "59") (name "unconnected-(U2-37{slash}PWM{slash}CS-Pad37)") (class "Default")
      (node (ref "U2") (pin "37") (pinfunction "37/PWM/CS_37") (pintype "passive"))
    )
    (net (code "60") (name "unconnected-(U2-38{slash}IN1{slash}CS1{slash}A14-Pad38)") (class "Default")
      (node (ref "U2") (pin "38") (pinfunction "38/IN1/CS1/A14_38") (pintype "passive"))
    )
    (net (code "61") (name "unconnected-(U2-39{slash}OUT1A{slash}MISO1{slash}A15-Pad39)") (class "Default")
      (node (ref "U2") (pin "39") (pinfunction "39/OUT1A/MISO1/A15_39") (pintype "passive"))
    )
    (net (code "62") (name "unconnected-(U2-40{slash}A16-Pad40)") (class "Default")
      (node (ref "U2") (pin "40") (pinfunction "40/A16_40") (pintype "passive"))
    )
    (net (code "63") (name "unconnected-(U2-41{slash}A17-Pad41)") (class "Default")
      (node (ref "U2") (pin "41") (pinfunction "41/A17_41") (pintype "passive"))
    )
    (net (code "64") (name "unconnected-(U5-A4-Pad5)") (class "Default")
      (node (ref "U5") (pin "5") (pinfunction "A4_5") (pintype "passive"))
    )
    (net (code "65") (name "unconnected-(U5-B4-Pad10)") (class "Default")
      (node (ref "U5") (pin "10") (pinfunction "B4_10") (pintype "passive"))
    )
    (net (code "66") (name "unconnected-(U14-INT1-Pad8)") (class "Default")
      (node (ref "U14") (pin "8") (pinfunction "INT1_8") (pintype "passive"))
    )
    (net (code "67") (name "unconnected-(U14-INT2-Pad9)") (class "Default")
      (node (ref "U14") (pin "9") (pinfunction "INT2_9") (pintype "passive"))
    )
    (net (code "68") (name "unconnected-(U16-INT1-Pad8)") (class "Default")
      (node (ref "U16") (pin "8") (pinfunction "INT1_8") (pintype "passive"))
    )
    (net (code "69") (name "unconnected-(U16-INT2-Pad9)") (class "Default")
      (node (ref "U16") (pin "9") (pinfunction "INT2_9") (pintype "passive"))
    )
    (net (code "70") (name "unconnected-(U17-INT1-Pad8)") (class "Default")
      (node (ref "U17") (pin "8") (pinfunction "INT1_8") (pintype "passive"))
    )
    (net (code "71") (name "unconnected-(U17-INT2-Pad9)") (class "Default")
      (node (ref "U17") (pin "9") (pinfunction "INT2_9") (pintype "passive"))
    )
    (net (code "72") (name "unconnected-(U19-INT1-Pad8)") (class "Default")
      (node (ref "U19") (pin "8") (pinfunction "INT1_8") (pintype "passive"))
    )
    (net (code "73") (name "unconnected-(U19-INT2-Pad9)") (class "Default")
      (node (ref "U19") (pin "9") (pinfunction "INT2_9") (pintype "passive"))
    )
  )
)
